# TEST_DCDC.net
KiCad netlist of a schematic drawn in EAGLE
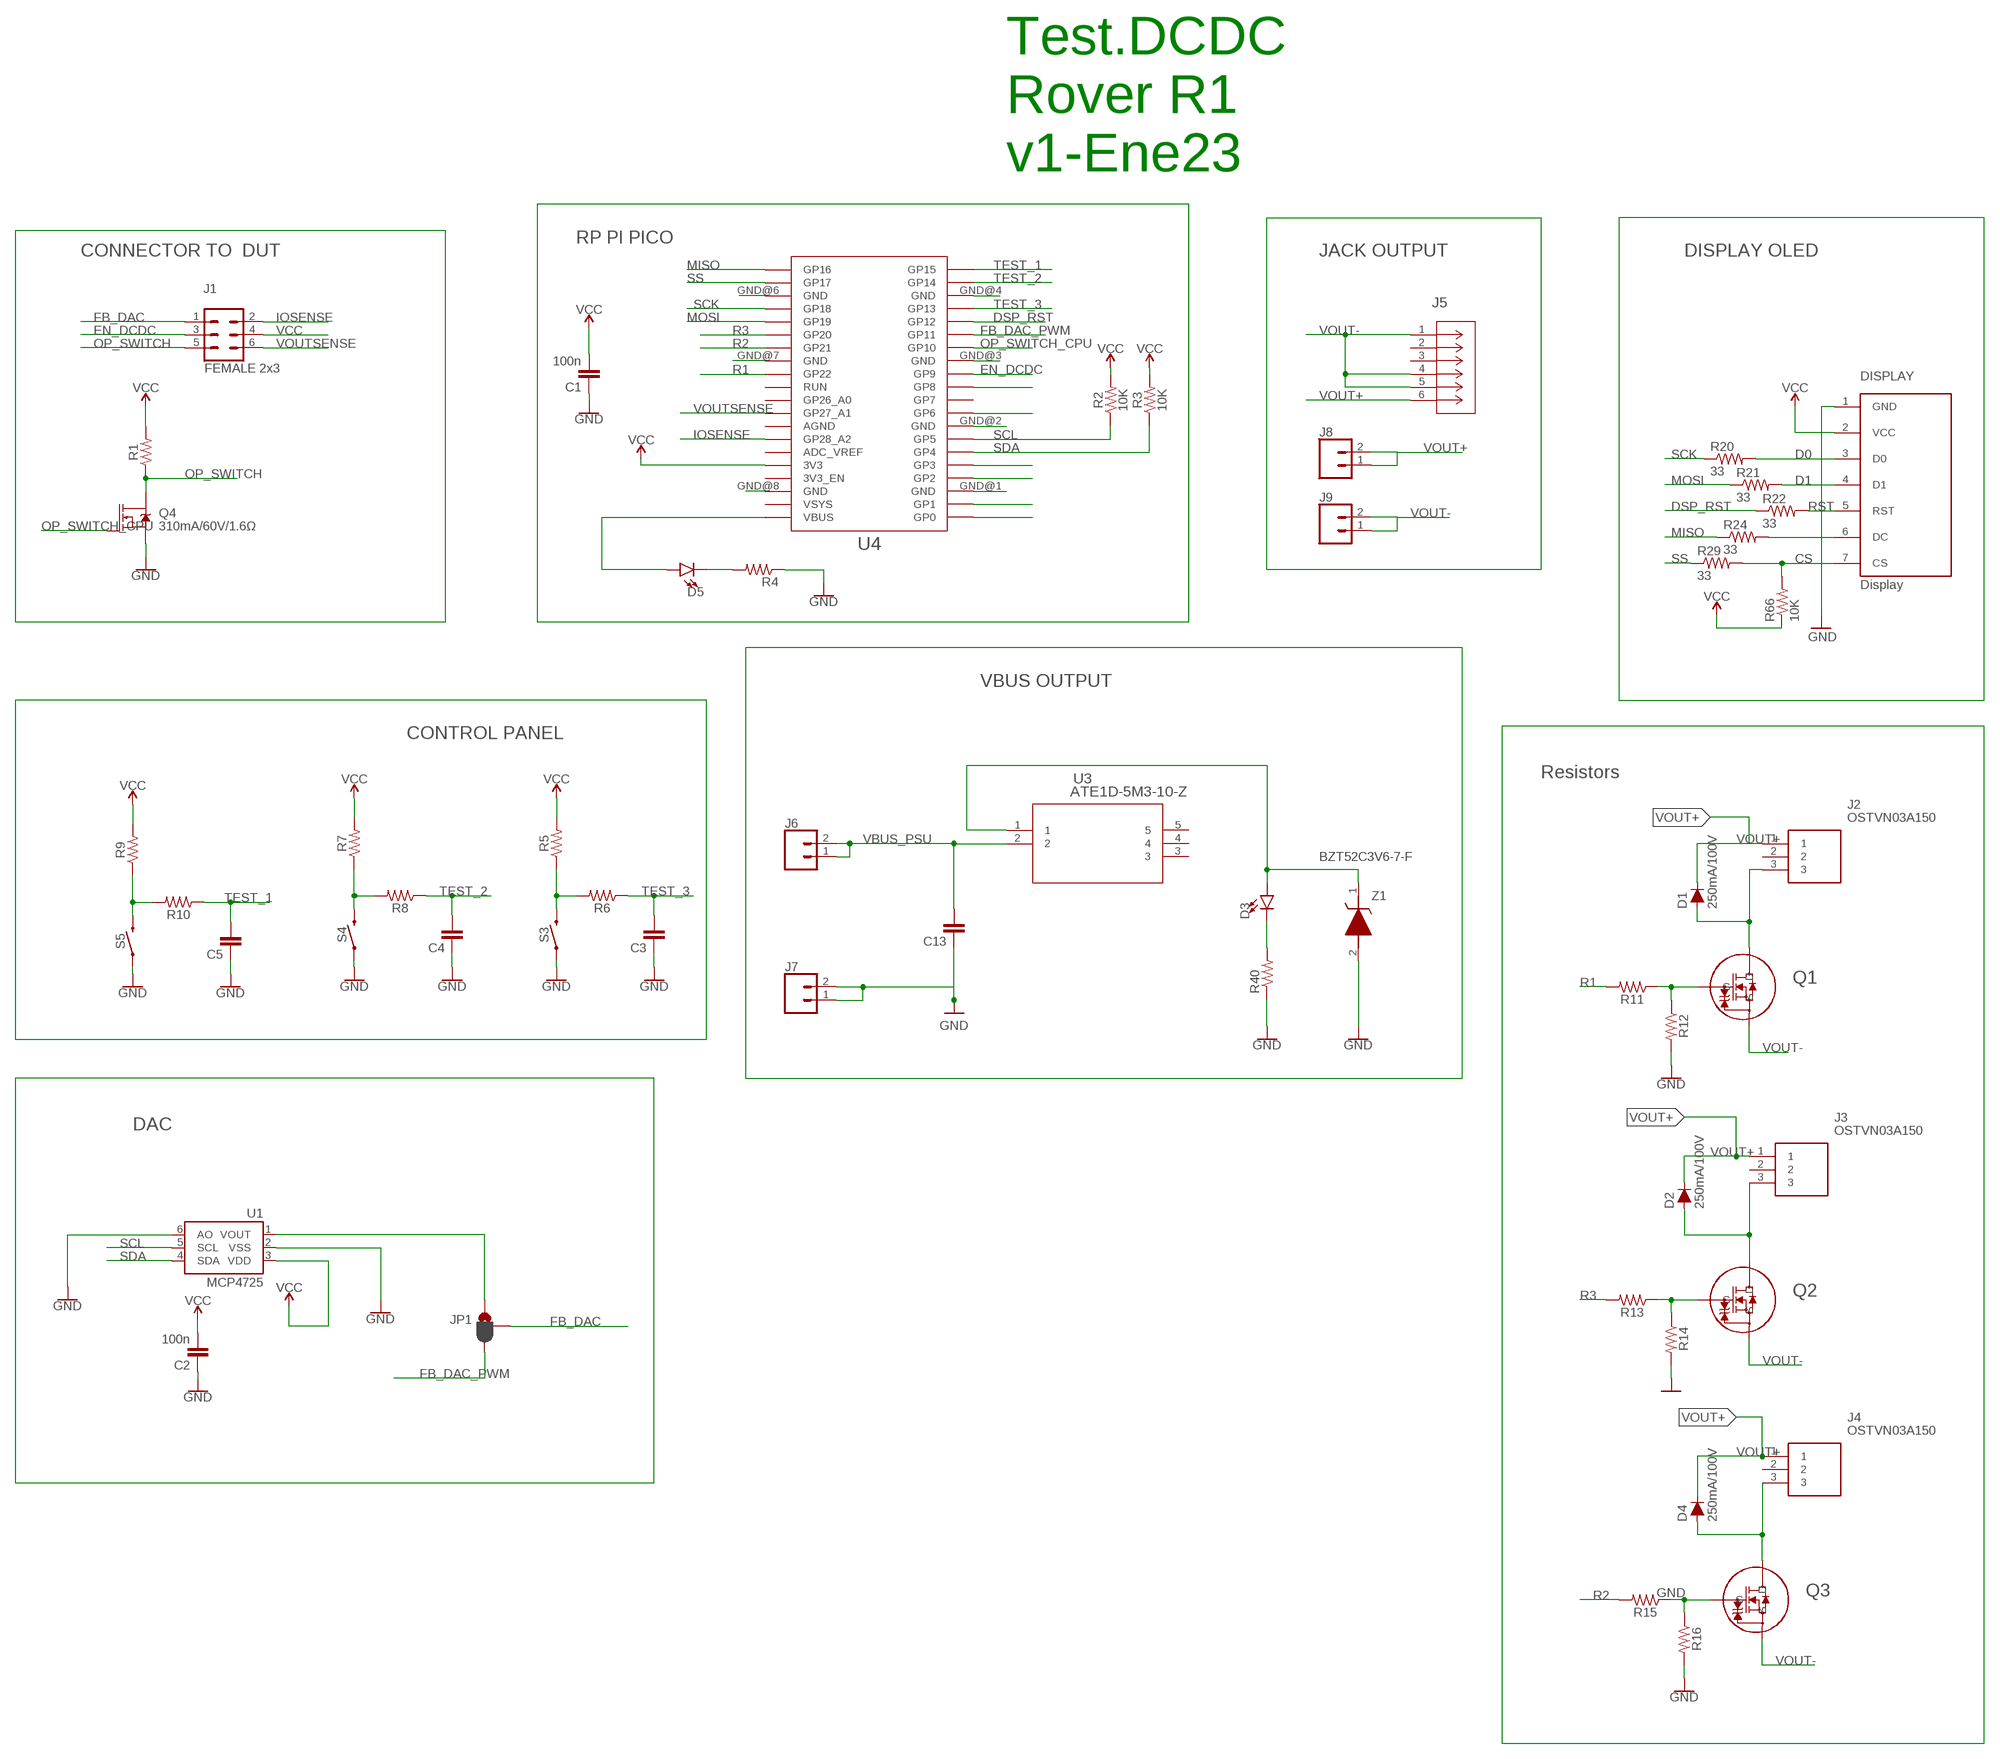
[diagram p0: schematic, sheet 1]

(export (version "E")
  (design (tool "Eeschema 10.0.6"))
  (components
    (comp (ref "C1")
      (value "100n")
      (footprint "eagle-import:C0805")
      (libsource (lib "eagle-import") (part "C-EUC0805"))
    )
    (comp (ref "C2")
      (value "100n")
      (footprint "eagle-import:C0805")
      (libsource (lib "eagle-import") (part "C-EUC0805"))
    )
    (comp (ref "C3")
      (value "C-EUC0805")
      (footprint "eagle-import:C0805")
      (libsource (lib "eagle-import") (part "C-EUC0805"))
    )
    (comp (ref "C4")
      (value "C-EUC0805")
      (footprint "eagle-import:C0805")
      (libsource (lib "eagle-import") (part "C-EUC0805"))
    )
    (comp (ref "C5")
      (value "C-EUC0805")
      (footprint "eagle-import:C0805")
      (libsource (lib "eagle-import") (part "C-EUC0805"))
    )
    (comp (ref "C13")
      (value "C-EUC0805")
      (footprint "eagle-import:C0805")
      (libsource (lib "eagle-import") (part "C-EUC0805"))
    )
    (comp (ref "D1")
      (value "250mA/100V")
      (footprint "eagle-import:SOD-323")
      (libsource (lib "eagle-import") (part "DIODE-BAS16J"))
    )
    (comp (ref "D2")
      (value "250mA/100V")
      (footprint "eagle-import:SOD-323")
      (libsource (lib "eagle-import") (part "DIODE-BAS16J"))
    )
    (comp (ref "D3")
      (value "LED3MM")
      (footprint "eagle-import:LED_3MM")
      (libsource (lib "eagle-import") (part "LED3MM"))
    )
    (comp (ref "D4")
      (value "250mA/100V")
      (footprint "eagle-import:SOD-323")
      (libsource (lib "eagle-import") (part "DIODE-BAS16J"))
    )
    (comp (ref "D5")
      (value "LED3MM")
      (footprint "eagle-import:LED_3MM")
      (libsource (lib "eagle-import") (part "LED3MM"))
    )
    (comp (ref "DISPLAY")
      (value "Display")
      (footprint "eagle-import:OLED_LCD")
      (libsource (lib "eagle-import") (part "OLED_LCD"))
    )
    (comp (ref "J1")
      (value "FEMALE 2x3")
      (footprint "eagle-import:2X3")
      (libsource (lib "eagle-import") (part "CONN_03X2FEMALE"))
    )
    (comp (ref "J2")
      (value "OSTVN03A150")
      (footprint "eagle-import:OSTVN03A150")
      (libsource (lib "eagle-import") (part "OSTVN03A150"))
    )
    (comp (ref "J3")
      (value "OSTVN03A150")
      (footprint "eagle-import:OSTVN03A150")
      (libsource (lib "eagle-import") (part "OSTVN03A150"))
    )
    (comp (ref "J4")
      (value "OSTVN03A150")
      (footprint "eagle-import:OSTVN03A150")
      (libsource (lib "eagle-import") (part "OSTVN03A150"))
    )
    (comp (ref "J5")
      (value "ACJS-MHDR")
      (footprint "eagle-import:CONN_MHDR_AMP")
      (fields (field (name "COPYRIGHT") "Copyright (C) 2018 Accelerated Designs. All rights reserved"))
      (libsource (lib "eagle-import") (part "ACJS-MHDR"))
    )
    (comp (ref "J6")
      (value "CONN_02")
      (footprint "eagle-import:1X02")
      (libsource (lib "eagle-import") (part "CONN_02"))
    )
    (comp (ref "J7")
      (value "CONN_02")
      (footprint "eagle-import:1X02")
      (libsource (lib "eagle-import") (part "CONN_02"))
    )
    (comp (ref "J8")
      (value "CONN_02")
      (footprint "eagle-import:1X02")
      (libsource (lib "eagle-import") (part "CONN_02"))
    )
    (comp (ref "J9")
      (value "CONN_02")
      (footprint "eagle-import:1X02")
      (libsource (lib "eagle-import") (part "CONN_02"))
    )
    (comp (ref "JP1")
      (value "JUMPER-SMT_3_1-NC_PASTE_SILK")
      (footprint "eagle-import:SMT-JUMPER_3_1-NC_PASTE_SILK")
      (libsource (lib "eagle-import") (part "JUMPER-SMT_3_1-NC_PASTE_SILK"))
    )
    (comp (ref "Q1")
      (value "PJA3416AE_R1_00001")
      (footprint "eagle-import:SOT23_PJA3416_PNJ")
      (fields (field (name "COPYRIGHT") "Copyright (C) 2022 Ultra Librarian. All rights reserved."))
      (libsource (lib "eagle-import") (part "PJA3416AE_R1_00001"))
    )
    (comp (ref "Q2")
      (value "PJA3416AE_R1_00001")
      (footprint "eagle-import:SOT23_PJA3416_PNJ")
      (fields (field (name "COPYRIGHT") "Copyright (C) 2022 Ultra Librarian. All rights reserved."))
      (libsource (lib "eagle-import") (part "PJA3416AE_R1_00001"))
    )
    (comp (ref "Q3")
      (value "PJA3416AE_R1_00001")
      (footprint "eagle-import:SOT23_PJA3416_PNJ")
      (fields (field (name "COPYRIGHT") "Copyright (C) 2022 Ultra Librarian. All rights reserved."))
      (libsource (lib "eagle-import") (part "PJA3416AE_R1_00001"))
    )
    (comp (ref "Q4")
      (value "310mA/60V/1.6Ω")
      (footprint "eagle-import:SOT323")
      (libsource (lib "eagle-import") (part "MOSFET-NCH-2N7002PW"))
    )
    (comp (ref "R1")
      (value "RESISTOR0805")
      (footprint "eagle-import:0805")
      (libsource (lib "eagle-import") (part "RESISTOR0805"))
    )
    (comp (ref "R2")
      (value "10K")
      (footprint "eagle-import:0805")
      (libsource (lib "eagle-import") (part "RESISTOR0805"))
    )
    (comp (ref "R3")
      (value "10K")
      (footprint "eagle-import:0805")
      (libsource (lib "eagle-import") (part "RESISTOR0805"))
    )
    (comp (ref "R4")
      (value "10K")
      (footprint "eagle-import:0805")
      (libsource (lib "eagle-import") (part "RESISTOR0805-RES"))
    )
    (comp (ref "R5")
      (value "RESISTOR0805")
      (footprint "eagle-import:0805")
      (libsource (lib "eagle-import") (part "RESISTOR0805"))
    )
    (comp (ref "R6")
      (value "RESISTOR0805")
      (footprint "eagle-import:0805")
      (libsource (lib "eagle-import") (part "RESISTOR0805"))
    )
    (comp (ref "R7")
      (value "RESISTOR0805")
      (footprint "eagle-import:0805")
      (libsource (lib "eagle-import") (part "RESISTOR0805"))
    )
    (comp (ref "R8")
      (value "RESISTOR0805")
      (footprint "eagle-import:0805")
      (libsource (lib "eagle-import") (part "RESISTOR0805"))
    )
    (comp (ref "R9")
      (value "RESISTOR0805")
      (footprint "eagle-import:0805")
      (libsource (lib "eagle-import") (part "RESISTOR0805"))
    )
    (comp (ref "R10")
      (value "RESISTOR0805")
      (footprint "eagle-import:0805")
      (libsource (lib "eagle-import") (part "RESISTOR0805"))
    )
    (comp (ref "R11")
      (value "RESISTOR0805")
      (footprint "eagle-import:0805")
      (libsource (lib "eagle-import") (part "RESISTOR0805"))
    )
    (comp (ref "R12")
      (value "RESISTOR0805")
      (footprint "eagle-import:0805")
      (libsource (lib "eagle-import") (part "RESISTOR0805"))
    )
    (comp (ref "R13")
      (value "RESISTOR0805")
      (footprint "eagle-import:0805")
      (libsource (lib "eagle-import") (part "RESISTOR0805"))
    )
    (comp (ref "R14")
      (value "RESISTOR0805")
      (footprint "eagle-import:0805")
      (libsource (lib "eagle-import") (part "RESISTOR0805"))
    )
    (comp (ref "R15")
      (value "RESISTOR0805")
      (footprint "eagle-import:0805")
      (libsource (lib "eagle-import") (part "RESISTOR0805"))
    )
    (comp (ref "R16")
      (value "RESISTOR0805")
      (footprint "eagle-import:0805")
      (libsource (lib "eagle-import") (part "RESISTOR0805"))
    )
    (comp (ref "R20")
      (value "33")
      (footprint "eagle-import:0805")
      (libsource (lib "eagle-import") (part "RESISTOR0805-RES"))
    )
    (comp (ref "R21")
      (value "33")
      (footprint "eagle-import:0805")
      (libsource (lib "eagle-import") (part "RESISTOR0805-RES"))
    )
    (comp (ref "R22")
      (value "33")
      (footprint "eagle-import:0805")
      (libsource (lib "eagle-import") (part "RESISTOR0805-RES"))
    )
    (comp (ref "R24")
      (value "33")
      (footprint "eagle-import:0805")
      (libsource (lib "eagle-import") (part "RESISTOR0805-RES"))
    )
    (comp (ref "R29")
      (value "33")
      (footprint "eagle-import:0805")
      (libsource (lib "eagle-import") (part "RESISTOR0805-RES"))
    )
    (comp (ref "R40")
      (value "10K")
      (footprint "eagle-import:0805")
      (libsource (lib "eagle-import") (part "RESISTOR0805-RES"))
    )
    (comp (ref "R66")
      (value "10K")
      (footprint "eagle-import:0805")
      (libsource (lib "eagle-import") (part "RESISTOR0805-RES"))
    )
    (comp (ref "S3")
      (value "MOMENTARY-SWITCH-SPST-SMD-5.2MM")
      (footprint "eagle-import:TACTILE_SWITCH_SMD_5.2MM")
      (libsource (lib "eagle-import") (part "MOMENTARY-SWITCH-SPST-SMD-5.2MM"))
    )
    (comp (ref "S4")
      (value "MOMENTARY-SWITCH-SPST-SMD-5.2MM")
      (footprint "eagle-import:TACTILE_SWITCH_SMD_5.2MM")
      (libsource (lib "eagle-import") (part "MOMENTARY-SWITCH-SPST-SMD-5.2MM"))
    )
    (comp (ref "S5")
      (value "MOMENTARY-SWITCH-SPST-SMD-5.2MM")
      (footprint "eagle-import:TACTILE_SWITCH_SMD_5.2MM")
      (libsource (lib "eagle-import") (part "MOMENTARY-SWITCH-SPST-SMD-5.2MM"))
    )
    (comp (ref "U1")
      (value "MCP4725")
      (footprint "eagle-import:SOT23-6")
      (libsource (lib "eagle-import") (part "MCP4725SOT-23"))
    )
    (comp (ref "U3")
      (value "ATE1D-5M3-10-Z")
      (footprint "eagle-import:SPDT05_ATE1D_9P5X8_NDC")
      (fields (field (name "COPYRIGHT") "Copyright (C) 2022 Ultra Librarian. All rights reserved."))
      (libsource (lib "eagle-import") (part "ATE1D-5M3-10-Z"))
    )
    (comp (ref "U4")
      (value "RPI_PICO_IG-TH")
      (footprint "eagle-import:RPI_PICO_TH")
      (libsource (lib "eagle-import") (part "RPI_PICO_IG-TH"))
    )
    (comp (ref "Z1")
      (value "BZT52C3V6-7-F")
      (footprint "eagle-import:SOD3716X135N")
      (fields (field (name "MOUSER_PART_NUMBER") "621-BZT52C3V6-F"))
      (libsource (lib "eagle-import") (part "BZT52C3V6-7-F"))
    )
  )
  (nets
    (net (code "1") (name "/CS") (class "Default")
      (node (ref "DISPLAY") (pin "7") (pinfunction "CS_7") (pintype "bidirectional"))
      (node (ref "R29") (pin "2") (pinfunction "2_2") (pintype "passive"))
      (node (ref "R66") (pin "2") (pinfunction "2_2") (pintype "passive"))
    )
    (net (code "2") (name "/D0") (class "Default")
      (node (ref "DISPLAY") (pin "3") (pinfunction "D0_3") (pintype "bidirectional"))
      (node (ref "R20") (pin "2") (pinfunction "2_2") (pintype "passive"))
    )
    (net (code "3") (name "/D1") (class "Default")
      (node (ref "DISPLAY") (pin "4") (pinfunction "D1_4") (pintype "bidirectional"))
      (node (ref "R21") (pin "2") (pinfunction "2_2") (pintype "passive"))
    )
    (net (code "4") (name "/DSP_RST") (class "Default")
      (node (ref "R22") (pin "1") (pinfunction "1_1") (pintype "passive"))
      (node (ref "U4") (pin "GP12") (pinfunction "GP12_GP12") (pintype "bidirectional"))
    )
    (net (code "5") (name "/EN_DCDC") (class "Default")
      (node (ref "J1") (pin "3") (pinfunction "3_3") (pintype "bidirectional"))
      (node (ref "U4") (pin "GP9") (pinfunction "GP9_GP9") (pintype "bidirectional"))
    )
    (net (code "6") (name "/FB_DAC") (class "Default")
      (node (ref "J1") (pin "1") (pinfunction "1_1") (pintype "bidirectional"))
      (node (ref "JP1") (pin "2") (pinfunction "2_2") (pintype "passive"))
    )
    (net (code "7") (name "/FB_DAC_PWM") (class "Default")
      (node (ref "JP1") (pin "3") (pinfunction "3_3") (pintype "passive"))
      (node (ref "U4") (pin "GP11") (pinfunction "GP11_GP11") (pintype "bidirectional"))
    )
    (net (code "8") (name "/IOSENSE") (class "Default")
      (node (ref "J1") (pin "2") (pinfunction "2_2") (pintype "bidirectional"))
      (node (ref "U4") (pin "GP28_A2") (pinfunction "GP28_A2_GP28_A2") (pintype "bidirectional"))
    )
    (net (code "9") (name "/MISO") (class "Default")
      (node (ref "R24") (pin "1") (pinfunction "1_1") (pintype "passive"))
      (node (ref "U4") (pin "GP16") (pinfunction "GP16_GP16") (pintype "bidirectional"))
    )
    (net (code "10") (name "/MOSI") (class "Default")
      (node (ref "R21") (pin "1") (pinfunction "1_1") (pintype "passive"))
      (node (ref "U4") (pin "GP19") (pinfunction "GP19_GP19") (pintype "bidirectional"))
    )
    (net (code "11") (name "/OP_SWITCH") (class "Default")
      (node (ref "J1") (pin "5") (pinfunction "5_5") (pintype "bidirectional"))
      (node (ref "Q4") (pin "3") (pinfunction "D_3") (pintype "bidirectional"))
      (node (ref "R1") (pin "1") (pinfunction "1_1") (pintype "passive"))
    )
    (net (code "12") (name "/OP_SWITCH_CPU") (class "Default")
      (node (ref "Q4") (pin "1") (pinfunction "G_1") (pintype "bidirectional"))
      (node (ref "U4") (pin "GP10") (pinfunction "GP10_GP10") (pintype "bidirectional"))
    )
    (net (code "13") (name "/R1") (class "Default")
      (node (ref "R11") (pin "2") (pinfunction "2_2") (pintype "passive"))
      (node (ref "U4") (pin "GP22") (pinfunction "GP22_GP22") (pintype "bidirectional"))
    )
    (net (code "14") (name "/R2") (class "Default")
      (node (ref "R15") (pin "2") (pinfunction "2_2") (pintype "passive"))
      (node (ref "U4") (pin "GP21") (pinfunction "GP21_GP21") (pintype "bidirectional"))
    )
    (net (code "15") (name "/R3") (class "Default")
      (node (ref "R13") (pin "2") (pinfunction "2_2") (pintype "passive"))
      (node (ref "U4") (pin "GP20") (pinfunction "GP20_GP20") (pintype "bidirectional"))
    )
    (net (code "16") (name "/RST") (class "Default")
      (node (ref "DISPLAY") (pin "5") (pinfunction "RST_5") (pintype "bidirectional"))
      (node (ref "R22") (pin "2") (pinfunction "2_2") (pintype "passive"))
    )
    (net (code "17") (name "/SCK") (class "Default")
      (node (ref "R20") (pin "1") (pinfunction "1_1") (pintype "passive"))
      (node (ref "U4") (pin "GP18") (pinfunction "GP18_GP18") (pintype "bidirectional"))
    )
    (net (code "18") (name "/SCL") (class "Default")
      (node (ref "R2") (pin "1") (pinfunction "1_1") (pintype "passive"))
      (node (ref "U1") (pin "5") (pinfunction "SCL_5") (pintype "bidirectional"))
      (node (ref "U4") (pin "GP5") (pinfunction "GP5_GP5") (pintype "bidirectional"))
    )
    (net (code "19") (name "/SDA") (class "Default")
      (node (ref "R3") (pin "1") (pinfunction "1_1") (pintype "passive"))
      (node (ref "U1") (pin "4") (pinfunction "SDA_4") (pintype "bidirectional"))
      (node (ref "U4") (pin "GP4") (pinfunction "GP4_GP4") (pintype "bidirectional"))
    )
    (net (code "20") (name "/SS") (class "Default")
      (node (ref "R29") (pin "1") (pinfunction "1_1") (pintype "passive"))
      (node (ref "U4") (pin "GP17") (pinfunction "GP17_GP17") (pintype "bidirectional"))
    )
    (net (code "21") (name "/TEST_1") (class "Default")
      (node (ref "C5") (pin "2") (pinfunction "2_2") (pintype "passive"))
      (node (ref "R10") (pin "1") (pinfunction "1_1") (pintype "passive"))
      (node (ref "U4") (pin "GP15") (pinfunction "GP15_GP15") (pintype "bidirectional"))
    )
    (net (code "22") (name "/TEST_2") (class "Default")
      (node (ref "C4") (pin "2") (pinfunction "2_2") (pintype "passive"))
      (node (ref "R8") (pin "1") (pinfunction "1_1") (pintype "passive"))
      (node (ref "U4") (pin "GP14") (pinfunction "GP14_GP14") (pintype "bidirectional"))
    )
    (net (code "23") (name "/TEST_3") (class "Default")
      (node (ref "C3") (pin "2") (pinfunction "2_2") (pintype "passive"))
      (node (ref "R6") (pin "1") (pinfunction "1_1") (pintype "passive"))
      (node (ref "U4") (pin "GP13") (pinfunction "GP13_GP13") (pintype "bidirectional"))
    )
    (net (code "24") (name "/VBUS_PSU") (class "Default")
      (node (ref "C13") (pin "2") (pinfunction "2_2") (pintype "passive"))
      (node (ref "J6") (pin "1") (pinfunction "1_1") (pintype "passive"))
      (node (ref "J6") (pin "2") (pinfunction "2_2") (pintype "passive"))
      (node (ref "U3") (pin "2") (pinfunction "2_2") (pintype "passive"))
    )
    (net (code "25") (name "/VOUT-") (class "Default")
      (node (ref "J5") (pin "1") (pinfunction "1_1") (pintype "passive"))
      (node (ref "J5") (pin "4") (pinfunction "4_4") (pintype "passive"))
      (node (ref "J5") (pin "5") (pinfunction "5_5") (pintype "passive"))
      (node (ref "J9") (pin "1") (pinfunction "1_1") (pintype "passive"))
      (node (ref "J9") (pin "2") (pinfunction "2_2") (pintype "passive"))
      (node (ref "Q1") (pin "2") (pinfunction "S_2") (pintype "passive"))
      (node (ref "Q2") (pin "2") (pinfunction "S_2") (pintype "passive"))
      (node (ref "Q3") (pin "2") (pinfunction "S_2") (pintype "passive"))
    )
    (net (code "26") (name "/VOUTSENSE") (class "Default")
      (node (ref "J1") (pin "6") (pinfunction "6_6") (pintype "bidirectional"))
      (node (ref "U4") (pin "GP27_A1") (pinfunction "GP27_A1_GP27_A1") (pintype "bidirectional"))
    )
    (net (code "27") (name "GND") (class "Default")
      (node (ref "C1") (pin "1") (pinfunction "1_1") (pintype "passive"))
      (node (ref "C13") (pin "1") (pinfunction "1_1") (pintype "passive"))
      (node (ref "C2") (pin "1") (pinfunction "1_1") (pintype "passive"))
      (node (ref "C3") (pin "1") (pinfunction "1_1") (pintype "passive"))
      (node (ref "C4") (pin "1") (pinfunction "1_1") (pintype "passive"))
      (node (ref "C5") (pin "1") (pinfunction "1_1") (pintype "passive"))
      (node (ref "DISPLAY") (pin "1") (pinfunction "GND_1") (pintype "bidirectional"))
      (node (ref "J7") (pin "1") (pinfunction "1_1") (pintype "passive"))
      (node (ref "J7") (pin "2") (pinfunction "2_2") (pintype "passive"))
      (node (ref "Q4") (pin "2") (pinfunction "S_2") (pintype "bidirectional"))
      (node (ref "R12") (pin "2") (pinfunction "2_2") (pintype "passive"))
      (node (ref "R14") (pin "2") (pinfunction "2_2") (pintype "passive"))
      (node (ref "R16") (pin "2") (pinfunction "2_2") (pintype "passive"))
      (node (ref "R4") (pin "1") (pinfunction "1_1") (pintype "passive"))
      (node (ref "R40") (pin "1") (pinfunction "1_1") (pintype "passive"))
      (node (ref "S3") (pin "1") (pinfunction "1_1") (pintype "passive"))
      (node (ref "S4") (pin "1") (pinfunction "1_1") (pintype "passive"))
      (node (ref "S5") (pin "1") (pinfunction "1_1") (pintype "passive"))
      (node (ref "U1") (pin "2") (pinfunction "VSS_2") (pintype "bidirectional"))
      (node (ref "U1") (pin "6") (pinfunction "AO_6") (pintype "bidirectional"))
      (node (ref "U4") (pin "GND@1") (pinfunction "GND_GND@1") (pintype "bidirectional"))
      (node (ref "U4") (pin "GND@2") (pinfunction "GND_GND@2") (pintype "bidirectional"))
      (node (ref "U4") (pin "GND@3") (pinfunction "GND_GND@3") (pintype "bidirectional"))
      (node (ref "U4") (pin "GND@4") (pinfunction "GND_GND@4") (pintype "bidirectional"))
      (node (ref "U4") (pin "GND@6") (pinfunction "GND_GND@6") (pintype "bidirectional"))
      (node (ref "U4") (pin "GND@7") (pinfunction "GND_GND@7") (pintype "bidirectional"))
      (node (ref "U4") (pin "GND@8") (pinfunction "GND_GND@8") (pintype "bidirectional"))
      (node (ref "Z1") (pin "2") (pinfunction "A_2") (pintype "bidirectional"))
    )
    (net (code "28") (name "Net-(D3-C)") (class "Default")
      (node (ref "D3") (pin "K") (pinfunction "C_K") (pintype "passive"))
      (node (ref "R40") (pin "2") (pinfunction "2_2") (pintype "passive"))
    )
    (net (code "29") (name "Net-(D5-C)") (class "Default")
      (node (ref "D5") (pin "K") (pinfunction "C_K") (pintype "passive"))
      (node (ref "R4") (pin "2") (pinfunction "2_2") (pintype "passive"))
    )
    (net (code "30") (name "Net-(D5-PadA)") (class "Default")
      (node (ref "D5") (pin "A") (pinfunction "A_A") (pintype "passive"))
      (node (ref "U4") (pin "VBUS") (pinfunction "VBUS_VBUS") (pintype "bidirectional"))
    )
    (net (code "31") (name "Net-(DISPLAY-DC)") (class "Default")
      (node (ref "DISPLAY") (pin "6") (pinfunction "DC_6") (pintype "bidirectional"))
      (node (ref "R24") (pin "2") (pinfunction "2_2") (pintype "passive"))
    )
    (net (code "32") (name "Net-(Q1-D)") (class "Default")
      (node (ref "D1") (pin "A") (pinfunction "A_A") (pintype "passive"))
      (node (ref "J2") (pin "3") (pinfunction "3_3") (pintype "bidirectional"))
      (node (ref "Q1") (pin "3") (pinfunction "D_3") (pintype "passive"))
    )
    (net (code "33") (name "Net-(Q1-G)") (class "Default")
      (node (ref "Q1") (pin "1") (pinfunction "G_1") (pintype "passive"))
      (node (ref "R11") (pin "1") (pinfunction "1_1") (pintype "passive"))
      (node (ref "R12") (pin "1") (pinfunction "1_1") (pintype "passive"))
    )
    (net (code "34") (name "Net-(Q2-D)") (class "Default")
      (node (ref "D2") (pin "A") (pinfunction "A_A") (pintype "passive"))
      (node (ref "J3") (pin "3") (pinfunction "3_3") (pintype "bidirectional"))
      (node (ref "Q2") (pin "3") (pinfunction "D_3") (pintype "passive"))
    )
    (net (code "35") (name "Net-(Q2-G)") (class "Default")
      (node (ref "Q2") (pin "1") (pinfunction "G_1") (pintype "passive"))
      (node (ref "R13") (pin "1") (pinfunction "1_1") (pintype "passive"))
      (node (ref "R14") (pin "1") (pinfunction "1_1") (pintype "passive"))
    )
    (net (code "36") (name "Net-(Q3-D)") (class "Default")
      (node (ref "D4") (pin "A") (pinfunction "A_A") (pintype "passive"))
      (node (ref "J4") (pin "3") (pinfunction "3_3") (pintype "bidirectional"))
      (node (ref "Q3") (pin "3") (pinfunction "D_3") (pintype "passive"))
    )
    (net (code "37") (name "Net-(Q3-G)") (class "Default")
      (node (ref "Q3") (pin "1") (pinfunction "G_1") (pintype "passive"))
      (node (ref "R15") (pin "1") (pinfunction "1_1") (pintype "passive"))
      (node (ref "R16") (pin "1") (pinfunction "1_1") (pintype "passive"))
    )
    (net (code "38") (name "Net-(S3-2)") (class "Default")
      (node (ref "R5") (pin "1") (pinfunction "1_1") (pintype "passive"))
      (node (ref "R6") (pin "2") (pinfunction "2_2") (pintype "passive"))
      (node (ref "S3") (pin "3") (pinfunction "2_3") (pintype "passive"))
    )
    (net (code "39") (name "Net-(S4-2)") (class "Default")
      (node (ref "R7") (pin "1") (pinfunction "1_1") (pintype "passive"))
      (node (ref "R8") (pin "2") (pinfunction "2_2") (pintype "passive"))
      (node (ref "S4") (pin "3") (pinfunction "2_3") (pintype "passive"))
    )
    (net (code "40") (name "Net-(S5-2)") (class "Default")
      (node (ref "R10") (pin "2") (pinfunction "2_2") (pintype "passive"))
      (node (ref "R9") (pin "1") (pinfunction "1_1") (pintype "passive"))
      (node (ref "S5") (pin "3") (pinfunction "2_3") (pintype "passive"))
    )
    (net (code "41") (name "Net-(U1-VOUT)") (class "Default")
      (node (ref "JP1") (pin "1") (pinfunction "1_1") (pintype "passive"))
      (node (ref "U1") (pin "1") (pinfunction "VOUT_1") (pintype "bidirectional"))
    )
    (net (code "42") (name "Net-(Z1-K)") (class "Default")
      (node (ref "D3") (pin "A") (pinfunction "A_A") (pintype "passive"))
      (node (ref "U3") (pin "1") (pinfunction "1_1") (pintype "passive"))
      (node (ref "Z1") (pin "1") (pinfunction "K_1") (pintype "bidirectional"))
    )
    (net (code "43") (name "VCC") (class "Default")
      (node (ref "C1") (pin "2") (pinfunction "2_2") (pintype "passive"))
      (node (ref "C2") (pin "2") (pinfunction "2_2") (pintype "passive"))
      (node (ref "DISPLAY") (pin "2") (pinfunction "VCC_2") (pintype "bidirectional"))
      (node (ref "J1") (pin "4") (pinfunction "4_4") (pintype "bidirectional"))
      (node (ref "R1") (pin "2") (pinfunction "2_2") (pintype "passive"))
      (node (ref "R2") (pin "2") (pinfunction "2_2") (pintype "passive"))
      (node (ref "R3") (pin "2") (pinfunction "2_2") (pintype "passive"))
      (node (ref "R5") (pin "2") (pinfunction "2_2") (pintype "passive"))
      (node (ref "R66") (pin "1") (pinfunction "1_1") (pintype "passive"))
      (node (ref "R7") (pin "2") (pinfunction "2_2") (pintype "passive"))
      (node (ref "R9") (pin "2") (pinfunction "2_2") (pintype "passive"))
      (node (ref "U1") (pin "3") (pinfunction "VDD_3") (pintype "bidirectional"))
      (node (ref "U4") (pin "3V3") (pinfunction "3V3_3V3") (pintype "bidirectional"))
    )
    (net (code "44") (name "VOUT+") (class "Default")
      (node (ref "D1") (pin "C") (pinfunction "C_C") (pintype "passive"))
      (node (ref "D2") (pin "C") (pinfunction "C_C") (pintype "passive"))
      (node (ref "D4") (pin "C") (pinfunction "C_C") (pintype "passive"))
      (node (ref "J2") (pin "1") (pinfunction "1_1") (pintype "bidirectional"))
      (node (ref "J3") (pin "1") (pinfunction "1_1") (pintype "bidirectional"))
      (node (ref "J4") (pin "1") (pinfunction "1_1") (pintype "bidirectional"))
      (node (ref "J5") (pin "6") (pinfunction "6_6") (pintype "passive"))
      (node (ref "J8") (pin "1") (pinfunction "1_1") (pintype "passive"))
      (node (ref "J8") (pin "2") (pinfunction "2_2") (pintype "passive"))
    )
    (net (code "45") (name "unconnected-(J2-Pad2)") (class "Default")
      (node (ref "J2") (pin "2") (pinfunction "2_2") (pintype "bidirectional"))
    )
    (net (code "46") (name "unconnected-(J3-Pad2)") (class "Default")
      (node (ref "J3") (pin "2") (pinfunction "2_2") (pintype "bidirectional"))
    )
    (net (code "47") (name "unconnected-(J4-Pad2)") (class "Default")
      (node (ref "J4") (pin "2") (pinfunction "2_2") (pintype "bidirectional"))
    )
    (net (code "48") (name "unconnected-(J5-Pad2)") (class "Default")
      (node (ref "J5") (pin "2") (pinfunction "2_2") (pintype "passive"))
    )
    (net (code "49") (name "unconnected-(J5-Pad3)") (class "Default")
      (node (ref "J5") (pin "3") (pinfunction "3_3") (pintype "passive"))
    )
    (net (code "50") (name "unconnected-(U3-Pad3)") (class "Default")
      (node (ref "U3") (pin "3") (pinfunction "3_3") (pintype "passive"))
    )
    (net (code "51") (name "unconnected-(U3-Pad4)") (class "Default")
      (node (ref "U3") (pin "4") (pinfunction "4_4") (pintype "passive"))
    )
    (net (code "52") (name "unconnected-(U3-Pad5)") (class "Default")
      (node (ref "U3") (pin "5") (pinfunction "5_5") (pintype "passive"))
    )
    (net (code "53") (name "unconnected-(U4-Pad3V3_EN)") (class "Default")
      (node (ref "U4") (pin "3V3_EN") (pinfunction "3V3_EN_3V3_EN") (pintype "bidirectional"))
    )
    (net (code "54") (name "unconnected-(U4-PadADC_VREF)") (class "Default")
      (node (ref "U4") (pin "ADC_VREF") (pinfunction "ADC_VREF_ADC_VREF") (pintype "bidirectional"))
    )
    (net (code "55") (name "unconnected-(U4-PadAGND)") (class "Default")
      (node (ref "U4") (pin "AGND") (pinfunction "AGND_AGND") (pintype "bidirectional"))
    )
    (net (code "56") (name "unconnected-(U4-PadGP0)") (class "Default")
      (node (ref "U4") (pin "GP0") (pinfunction "GP0_GP0") (pintype "bidirectional"))
    )
    (net (code "57") (name "unconnected-(U4-PadGP1)") (class "Default")
      (node (ref "U4") (pin "GP1") (pinfunction "GP1_GP1") (pintype "bidirectional"))
    )
    (net (code "58") (name "unconnected-(U4-PadGP2)") (class "Default")
      (node (ref "U4") (pin "GP2") (pinfunction "GP2_GP2") (pintype "bidirectional"))
    )
    (net (code "59") (name "unconnected-(U4-PadGP3)") (class "Default")
      (node (ref "U4") (pin "GP3") (pinfunction "GP3_GP3") (pintype "bidirectional"))
    )
    (net (code "60") (name "unconnected-(U4-PadGP6)") (class "Default")
      (node (ref "U4") (pin "GP6") (pinfunction "GP6_GP6") (pintype "bidirectional"))
    )
    (net (code "61") (name "unconnected-(U4-PadGP7)") (class "Default")
      (node (ref "U4") (pin "GP7") (pinfunction "GP7_GP7") (pintype "bidirectional"))
    )
    (net (code "62") (name "unconnected-(U4-PadGP8)") (class "Default")
      (node (ref "U4") (pin "GP8") (pinfunction "GP8_GP8") (pintype "bidirectional"))
    )
    (net (code "63") (name "unconnected-(U4-PadGP26_A0)") (class "Default")
      (node (ref "U4") (pin "GP26_A0") (pinfunction "GP26_A0_GP26_A0") (pintype "bidirectional"))
    )
    (net (code "64") (name "unconnected-(U4-PadRUN)") (class "Default")
      (node (ref "U4") (pin "RUN") (pinfunction "RUN_RUN") (pintype "bidirectional"))
    )
    (net (code "65") (name "unconnected-(U4-PadVSYS)") (class "Default")
      (node (ref "U4") (pin "VSYS") (pinfunction "VSYS_VSYS") (pintype "bidirectional"))
    )
  )
)
